# RPL_POWER_24V.net
KiCad netlist of a schematic drawn in Altium Designer
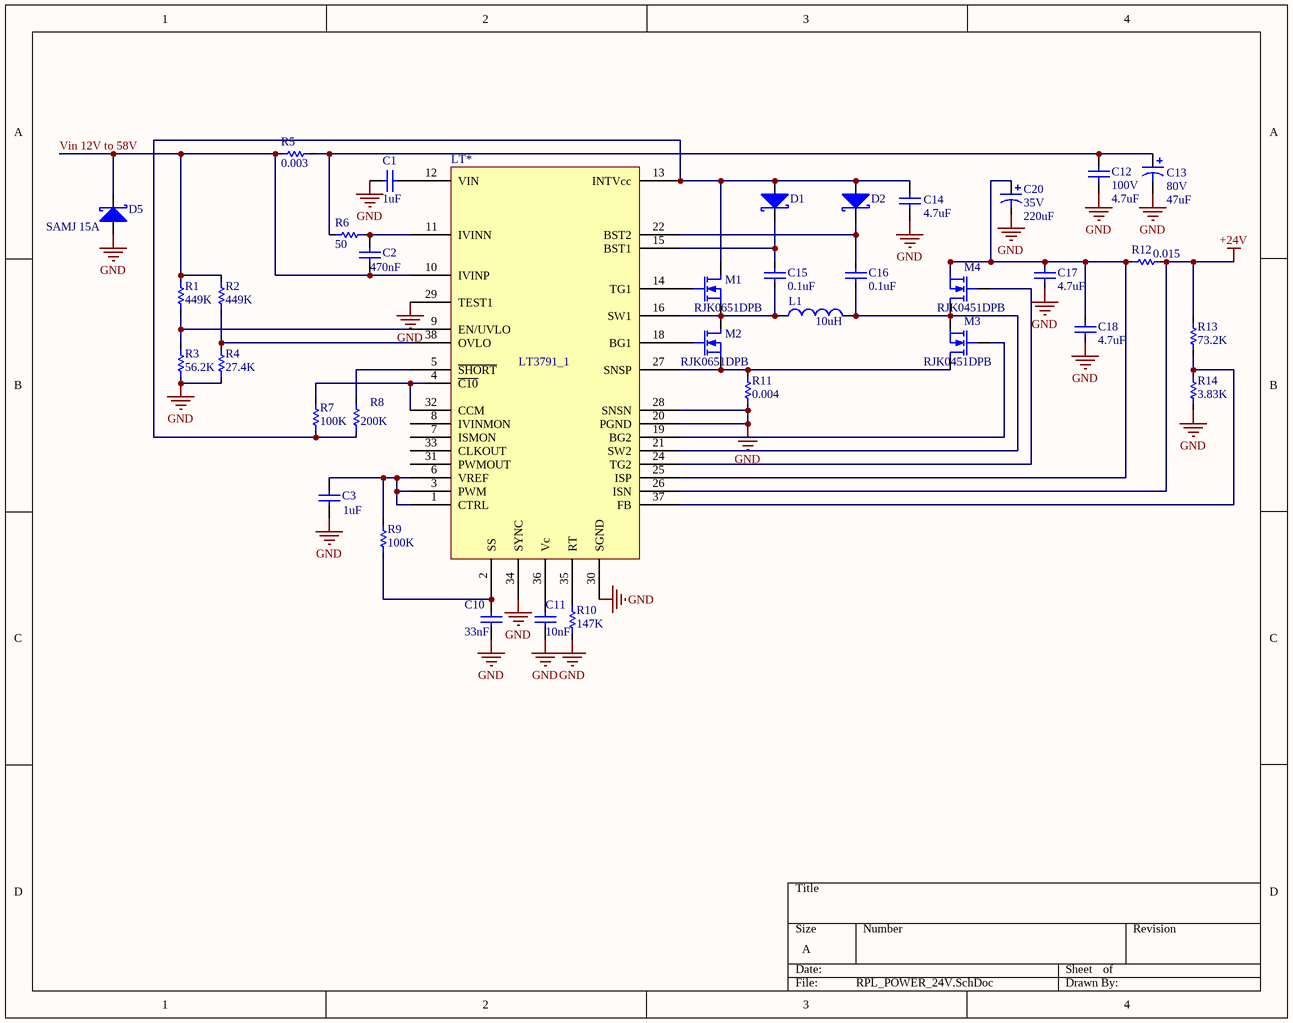
[diagram p0: RPL_POWER_24V.SchDoc]

(export (version "E")
  (design (tool "Eeschema 10.0.6"))
  (components
    (comp (ref "C1")
      (value "1uF")
      (footprint "C1206")
      (description "Capacitor (Semiconductor SIM Model)")
      (fields (field (name "Comment") "Cap Semi") (field (name "PUBLISHER") "Altium Limited"))
      (libsource (lib "Miscellaneous Devices") (part "Cap Semi"))
    )
    (comp (ref "C2")
      (value "470nF")
      (footprint "C1206")
      (description "Capacitor (Semiconductor SIM Model)")
      (fields (field (name "Comment") "Cap Semi") (field (name "PUBLISHER") "Altium Limited"))
      (libsource (lib "Miscellaneous Devices") (part "Cap Semi"))
    )
    (comp (ref "C3")
      (value "1uF")
      (footprint "C1206")
      (description "Capacitor (Semiconductor SIM Model)")
      (fields (field (name "Comment") "Cap Semi") (field (name "PUBLISHER") "Altium Limited"))
      (libsource (lib "Miscellaneous Devices") (part "Cap Semi"))
    )
    (comp (ref "C10")
      (value "33nF")
      (footprint "C1206")
      (description "Capacitor (Semiconductor SIM Model)")
      (fields (field (name "Comment") "Cap Semi") (field (name "PUBLISHER") "Altium Limited"))
      (libsource (lib "Miscellaneous Devices") (part "Cap Semi"))
    )
    (comp (ref "C11")
      (value "10nF")
      (footprint "C1206")
      (description "Capacitor (Semiconductor SIM Model)")
      (fields (field (name "Comment") "Cap Semi") (field (name "PUBLISHER") "Altium Limited"))
      (libsource (lib "Miscellaneous Devices") (part "Cap Semi"))
    )
    (comp (ref "C12")
      (value "100V")
      (footprint "C1206")
      (description "Capacitor (Semiconductor SIM Model)")
      (fields (field (name "ALTIUM_VALUE") "4.7uF") (field (name "PUBLISHER") "Altium Limited"))
      (libsource (lib "Miscellaneous Devices") (part "Cap Semi"))
    )
    (comp (ref "C13")
      (value "80V")
      (footprint "C0805")
      (description "Polarized Capacitor (Surface Mount)")
      (fields (field (name "ALTIUM_VALUE") "47uF") (field (name "PUBLISHER") "Altium Limited"))
      (libsource (lib "Miscellaneous Devices") (part "Cap Pol3"))
    )
    (comp (ref "C14")
      (value "4.7uF")
      (footprint "C1206")
      (description "Capacitor (Semiconductor SIM Model)")
      (fields (field (name "Comment") "Cap Semi") (field (name "PUBLISHER") "Altium Limited"))
      (libsource (lib "Miscellaneous Devices") (part "Cap Semi"))
    )
    (comp (ref "C15")
      (value "0.1uF")
      (fields (field (name "Comment") "Cap"))
      (libsource (lib "Generic_Library") (part "Cap"))
    )
    (comp (ref "C16")
      (value "0.1uF")
      (fields (field (name "Comment") "Cap"))
      (libsource (lib "Generic_Library") (part "Cap"))
    )
    (comp (ref "C17")
      (value "4.7uF")
      (fields (field (name "Comment") "50V"))
      (libsource (lib "Generic_Library") (part "Cap"))
    )
    (comp (ref "C18")
      (value "4.7uF")
      (fields (field (name "Comment") "50V"))
      (libsource (lib "Generic_Library") (part "Cap"))
    )
    (comp (ref "C20")
      (value "35V")
      (fields (field (name "ALTIUM_VALUE") "220uF"))
      (libsource (lib "Generic_Library") (part "Cap Elec"))
    )
    (comp (ref "D1") (value "Diod") (libsource (lib "Generic_Library") (part "Diod")))
    (comp (ref "D2") (value "Diod") (libsource (lib "Generic_Library") (part "Diod")))
    (comp (ref "D5") (value "SAMJ 15A") (libsource (lib "Generic_Library") (part "Diod")))
    (comp (ref "L1")
      (value "10uH")
      (fields (field (name "Comment") "Inductor"))
      (libsource (lib "Generic_Library") (part "Inductor"))
    )
    (comp (ref "LT*") (value "LT3791_1") (libsource (lib "Generic_Library") (part "LT3791_1")))
    (comp (ref "M1") (value "RJK0651DPB") (libsource (lib "Generic_Library") (part "Mosfet")))
    (comp (ref "M2") (value "RJK0651DPB") (libsource (lib "Generic_Library") (part "Mosfet")))
    (comp (ref "M3") (value "RJK0451DPB") (libsource (lib "Generic_Library") (part "Mosfet")))
    (comp (ref "M4") (value "RJK0451DPB") (libsource (lib "Generic_Library") (part "Mosfet")))
    (comp (ref "R1")
      (value "449K")
      (fields (field (name "Comment") "Res"))
      (libsource (lib "Generic_Library") (part "Res"))
    )
    (comp (ref "R2")
      (value "449K")
      (fields (field (name "Comment") "Res"))
      (libsource (lib "Generic_Library") (part "Res"))
    )
    (comp (ref "R3")
      (value "56.2K")
      (fields (field (name "Comment") "Res"))
      (libsource (lib "Generic_Library") (part "Res"))
    )
    (comp (ref "R4")
      (value "27.4K")
      (fields (field (name "Comment") "Res"))
      (libsource (lib "Generic_Library") (part "Res"))
    )
    (comp (ref "R5")
      (value "0.003")
      (fields (field (name "Comment") "Res"))
      (libsource (lib "Generic_Library") (part "Res"))
    )
    (comp (ref "R6")
      (value "50")
      (fields (field (name "Comment") "Res"))
      (libsource (lib "Generic_Library") (part "Res"))
    )
    (comp (ref "R7")
      (value "100K")
      (fields (field (name "Comment") "Res"))
      (libsource (lib "Generic_Library") (part "Res"))
    )
    (comp (ref "R8")
      (value "200K")
      (fields (field (name "Comment") "Res"))
      (libsource (lib "Generic_Library") (part "Res"))
    )
    (comp (ref "R9")
      (value "100K")
      (fields (field (name "Comment") "Res"))
      (libsource (lib "Generic_Library") (part "Res"))
    )
    (comp (ref "R10")
      (value "147K")
      (fields (field (name "Comment") "200KHz"))
      (libsource (lib "Generic_Library") (part "Res"))
    )
    (comp (ref "R11")
      (value "0.004")
      (fields (field (name "Comment") "Res"))
      (libsource (lib "Generic_Library") (part "Res"))
    )
    (comp (ref "R12")
      (value "0.015")
      (fields (field (name "Comment") "Res"))
      (libsource (lib "Generic_Library") (part "Res"))
    )
    (comp (ref "R13")
      (value "73.2K")
      (fields (field (name "Comment") "Res"))
      (libsource (lib "Generic_Library") (part "Res"))
    )
    (comp (ref "R14")
      (value "3.83K")
      (fields (field (name "Comment") "Res"))
      (libsource (lib "Generic_Library") (part "Res"))
    )
  )
  (nets
    (net (code "1") (name "+24V") (class "Default")
      (node (ref "LT*") (pin "26") (pinfunction "ISN_26") (pintype "passive"))
      (node (ref "R12") (pin "2") (pinfunction "2_2") (pintype "passive"))
      (node (ref "R13") (pin "2") (pinfunction "2_2") (pintype "passive"))
    )
    (net (code "2") (name "/Vin 12V to 58V") (class "Default")
      (node (ref "C2") (pin "1") (pinfunction "1_1") (pintype "passive"))
      (node (ref "D5") (pin "3") (pinfunction "K_3") (pintype "passive"))
      (node (ref "LT*") (pin "10") (pinfunction "IVINP_10") (pintype "passive"))
      (node (ref "R1") (pin "2") (pinfunction "2_2") (pintype "passive"))
      (node (ref "R2") (pin "2") (pinfunction "2_2") (pintype "passive"))
      (node (ref "R5") (pin "1") (pinfunction "1_1") (pintype "passive"))
    )
    (net (code "3") (name "GND") (class "Default")
      (node (ref "C1") (pin "2") (pinfunction "2_2") (pintype "passive"))
      (node (ref "C10") (pin "1") (pinfunction "1_1") (pintype "passive"))
      (node (ref "C11") (pin "1") (pinfunction "1_1") (pintype "passive"))
      (node (ref "C12") (pin "1") (pinfunction "1_1") (pintype "passive"))
      (node (ref "C13") (pin "2") (pinfunction "2_2") (pintype "passive"))
      (node (ref "C14") (pin "1") (pinfunction "1_1") (pintype "passive"))
      (node (ref "C17") (pin "1") (pinfunction "1_1") (pintype "passive"))
      (node (ref "C18") (pin "1") (pinfunction "1_1") (pintype "passive"))
      (node (ref "C20") (pin "2") (pinfunction "2_2") (pintype "passive"))
      (node (ref "C3") (pin "1") (pinfunction "1_1") (pintype "passive"))
      (node (ref "D5") (pin "1") (pinfunction "A_1") (pintype "passive"))
      (node (ref "LT*") (pin "20") (pinfunction "PGND_20") (pintype "passive"))
      (node (ref "LT*") (pin "28") (pinfunction "SNSN_28") (pintype "passive"))
      (node (ref "LT*") (pin "29") (pinfunction "TEST1_29") (pintype "passive"))
      (node (ref "LT*") (pin "30") (pinfunction "SGND_30") (pintype "passive"))
      (node (ref "LT*") (pin "34") (pinfunction "SYNC_34") (pintype "passive"))
      (node (ref "R10") (pin "1") (pinfunction "1_1") (pintype "passive"))
      (node (ref "R11") (pin "1") (pinfunction "1_1") (pintype "passive"))
      (node (ref "R14") (pin "1") (pinfunction "1_1") (pintype "passive"))
      (node (ref "R3") (pin "1") (pinfunction "1_1") (pintype "passive"))
      (node (ref "R4") (pin "1") (pinfunction "1_1") (pintype "passive"))
    )
    (net (code "4") (name "Net-(C12-Pad2)") (class "Default")
      (node (ref "C12") (pin "2") (pinfunction "2_2") (pintype "passive"))
      (node (ref "C13") (pin "1") (pinfunction "1_1") (pintype "passive"))
      (node (ref "R5") (pin "2") (pinfunction "2_2") (pintype "passive"))
      (node (ref "R6") (pin "1") (pinfunction "1_1") (pintype "passive"))
    )
    (net (code "5") (name "Net-(D1-A)") (class "Default")
      (node (ref "C14") (pin "2") (pinfunction "2_2") (pintype "passive"))
      (node (ref "D1") (pin "1") (pinfunction "A_1") (pintype "passive"))
      (node (ref "D2") (pin "1") (pinfunction "A_1") (pintype "passive"))
      (node (ref "LT*") (pin "13") (pinfunction "INTVcc_13") (pintype "passive"))
      (node (ref "M1") (pin "1") (pinfunction "D_1") (pintype "passive"))
      (node (ref "R7") (pin "1") (pinfunction "1_1") (pintype "passive"))
      (node (ref "R8") (pin "1") (pinfunction "1_1") (pintype "passive"))
    )
    (net (code "6") (name "Net-(D1-K)") (class "Default")
      (node (ref "C15") (pin "2") (pinfunction "2_2") (pintype "passive"))
      (node (ref "D1") (pin "3") (pinfunction "K_3") (pintype "passive"))
      (node (ref "LT*") (pin "15") (pinfunction "BST1_15") (pintype "passive"))
    )
    (net (code "7") (name "Net-(D2-K)") (class "Default")
      (node (ref "C16") (pin "2") (pinfunction "2_2") (pintype "passive"))
      (node (ref "D2") (pin "3") (pinfunction "K_3") (pintype "passive"))
      (node (ref "LT*") (pin "22") (pinfunction "BST2_22") (pintype "passive"))
    )
    (net (code "8") (name "Net-(LT*-BG1)") (class "Default")
      (node (ref "LT*") (pin "18") (pinfunction "BG1_18") (pintype "passive"))
      (node (ref "M2") (pin "2") (pinfunction "G_2") (pintype "passive"))
    )
    (net (code "9") (name "Net-(LT*-BG2)") (class "Default")
      (node (ref "LT*") (pin "19") (pinfunction "BG2_19") (pintype "passive"))
      (node (ref "M3") (pin "2") (pinfunction "G_2") (pintype "passive"))
    )
    (net (code "10") (name "Net-(LT*-CCM)") (class "Default")
      (node (ref "LT*") (pin "32") (pinfunction "CCM_32") (pintype "passive"))
      (node (ref "LT*") (pin "4") (pinfunction "~{C10}_4") (pintype "passive"))
      (node (ref "R7") (pin "2") (pinfunction "2_2") (pintype "passive"))
    )
    (net (code "11") (name "Net-(LT*-CTRL)") (class "Default")
      (node (ref "C3") (pin "2") (pinfunction "2_2") (pintype "passive"))
      (node (ref "LT*") (pin "1") (pinfunction "CTRL_1") (pintype "passive"))
      (node (ref "LT*") (pin "3") (pinfunction "PWM_3") (pintype "passive"))
      (node (ref "LT*") (pin "6") (pinfunction "VREF_6") (pintype "passive"))
      (node (ref "R9") (pin "2") (pinfunction "2_2") (pintype "passive"))
    )
    (net (code "12") (name "Net-(LT*-EN{slash}UVLO)") (class "Default")
      (node (ref "LT*") (pin "9") (pinfunction "EN/UVLO_9") (pintype "passive"))
      (node (ref "R1") (pin "1") (pinfunction "1_1") (pintype "passive"))
      (node (ref "R3") (pin "2") (pinfunction "2_2") (pintype "passive"))
    )
    (net (code "13") (name "Net-(LT*-FB)") (class "Default")
      (node (ref "LT*") (pin "37") (pinfunction "FB_37") (pintype "passive"))
      (node (ref "R13") (pin "1") (pinfunction "1_1") (pintype "passive"))
      (node (ref "R14") (pin "2") (pinfunction "2_2") (pintype "passive"))
    )
    (net (code "14") (name "Net-(LT*-ISP)") (class "Default")
      (node (ref "C17") (pin "2") (pinfunction "2_2") (pintype "passive"))
      (node (ref "C18") (pin "2") (pinfunction "2_2") (pintype "passive"))
      (node (ref "C20") (pin "1") (pinfunction "1_1") (pintype "passive"))
      (node (ref "LT*") (pin "25") (pinfunction "ISP_25") (pintype "passive"))
      (node (ref "M4") (pin "3") (pinfunction "S_3") (pintype "passive"))
      (node (ref "R12") (pin "1") (pinfunction "1_1") (pintype "passive"))
    )
    (net (code "15") (name "Net-(LT*-IVINN)") (class "Default")
      (node (ref "C2") (pin "2") (pinfunction "2_2") (pintype "passive"))
      (node (ref "LT*") (pin "11") (pinfunction "IVINN_11") (pintype "passive"))
      (node (ref "R6") (pin "2") (pinfunction "2_2") (pintype "passive"))
    )
    (net (code "16") (name "Net-(LT*-OVLO)") (class "Default")
      (node (ref "LT*") (pin "38") (pinfunction "OVLO_38") (pintype "passive"))
      (node (ref "R2") (pin "1") (pinfunction "1_1") (pintype "passive"))
      (node (ref "R4") (pin "2") (pinfunction "2_2") (pintype "passive"))
    )
    (net (code "17") (name "Net-(LT*-RT)") (class "Default")
      (node (ref "LT*") (pin "35") (pinfunction "RT_35") (pintype "passive"))
      (node (ref "R10") (pin "2") (pinfunction "2_2") (pintype "passive"))
    )
    (net (code "18") (name "Net-(LT*-SNSP)") (class "Default")
      (node (ref "LT*") (pin "27") (pinfunction "SNSP_27") (pintype "passive"))
      (node (ref "M2") (pin "3") (pinfunction "S_3") (pintype "passive"))
      (node (ref "M3") (pin "1") (pinfunction "D_1") (pintype "passive"))
      (node (ref "R11") (pin "2") (pinfunction "2_2") (pintype "passive"))
    )
    (net (code "19") (name "Net-(LT*-SS)") (class "Default")
      (node (ref "C10") (pin "2") (pinfunction "2_2") (pintype "passive"))
      (node (ref "LT*") (pin "2") (pinfunction "SS_2") (pintype "passive"))
      (node (ref "R9") (pin "1") (pinfunction "1_1") (pintype "passive"))
    )
    (net (code "20") (name "Net-(LT*-SW1)") (class "Default")
      (node (ref "C15") (pin "1") (pinfunction "1_1") (pintype "passive"))
      (node (ref "L1") (pin "1") (pinfunction "1_1") (pintype "passive"))
      (node (ref "LT*") (pin "16") (pinfunction "SW1_16") (pintype "passive"))
      (node (ref "M1") (pin "3") (pinfunction "S_3") (pintype "passive"))
      (node (ref "M2") (pin "1") (pinfunction "D_1") (pintype "passive"))
    )
    (net (code "21") (name "Net-(LT*-SW2)") (class "Default")
      (node (ref "C16") (pin "1") (pinfunction "1_1") (pintype "passive"))
      (node (ref "L1") (pin "2") (pinfunction "2_2") (pintype "passive"))
      (node (ref "LT*") (pin "21") (pinfunction "SW2_21") (pintype "passive"))
      (node (ref "M3") (pin "3") (pinfunction "S_3") (pintype "passive"))
      (node (ref "M4") (pin "1") (pinfunction "D_1") (pintype "passive"))
    )
    (net (code "22") (name "Net-(LT*-TG1)") (class "Default")
      (node (ref "LT*") (pin "14") (pinfunction "TG1_14") (pintype "passive"))
      (node (ref "M1") (pin "2") (pinfunction "G_2") (pintype "passive"))
    )
    (net (code "23") (name "Net-(LT*-TG2)") (class "Default")
      (node (ref "LT*") (pin "24") (pinfunction "TG2_24") (pintype "passive"))
      (node (ref "M4") (pin "2") (pinfunction "G_2") (pintype "passive"))
    )
    (net (code "24") (name "Net-(LT*-VIN)") (class "Default")
      (node (ref "C1") (pin "1") (pinfunction "1_1") (pintype "passive"))
      (node (ref "LT*") (pin "12") (pinfunction "VIN_12") (pintype "passive"))
    )
    (net (code "25") (name "Net-(LT*-Vc)") (class "Default")
      (node (ref "C11") (pin "2") (pinfunction "2_2") (pintype "passive"))
      (node (ref "LT*") (pin "36") (pinfunction "Vc_36") (pintype "passive"))
    )
    (net (code "26") (name "Net-(LT*-~{SHORT})") (class "Default")
      (node (ref "LT*") (pin "5") (pinfunction "~{SHORT}_5") (pintype "passive"))
      (node (ref "R8") (pin "2") (pinfunction "2_2") (pintype "passive"))
    )
    (net (code "27") (name "unconnected-(LT*-CLKOUT-Pad33)") (class "Default")
      (node (ref "LT*") (pin "33") (pinfunction "CLKOUT_33") (pintype "passive"))
    )
    (net (code "28") (name "unconnected-(LT*-ISMON-Pad7)") (class "Default")
      (node (ref "LT*") (pin "7") (pinfunction "ISMON_7") (pintype "passive"))
    )
    (net (code "29") (name "unconnected-(LT*-IVINMON-Pad8)") (class "Default")
      (node (ref "LT*") (pin "8") (pinfunction "IVINMON_8") (pintype "passive"))
    )
    (net (code "30") (name "unconnected-(LT*-PWMOUT-Pad31)") (class "Default")
      (node (ref "LT*") (pin "31") (pinfunction "PWMOUT_31") (pintype "passive"))
    )
  )
)
